# EBN_DUAL_V01.net
KiCad netlist of a schematic drawn in EAGLE
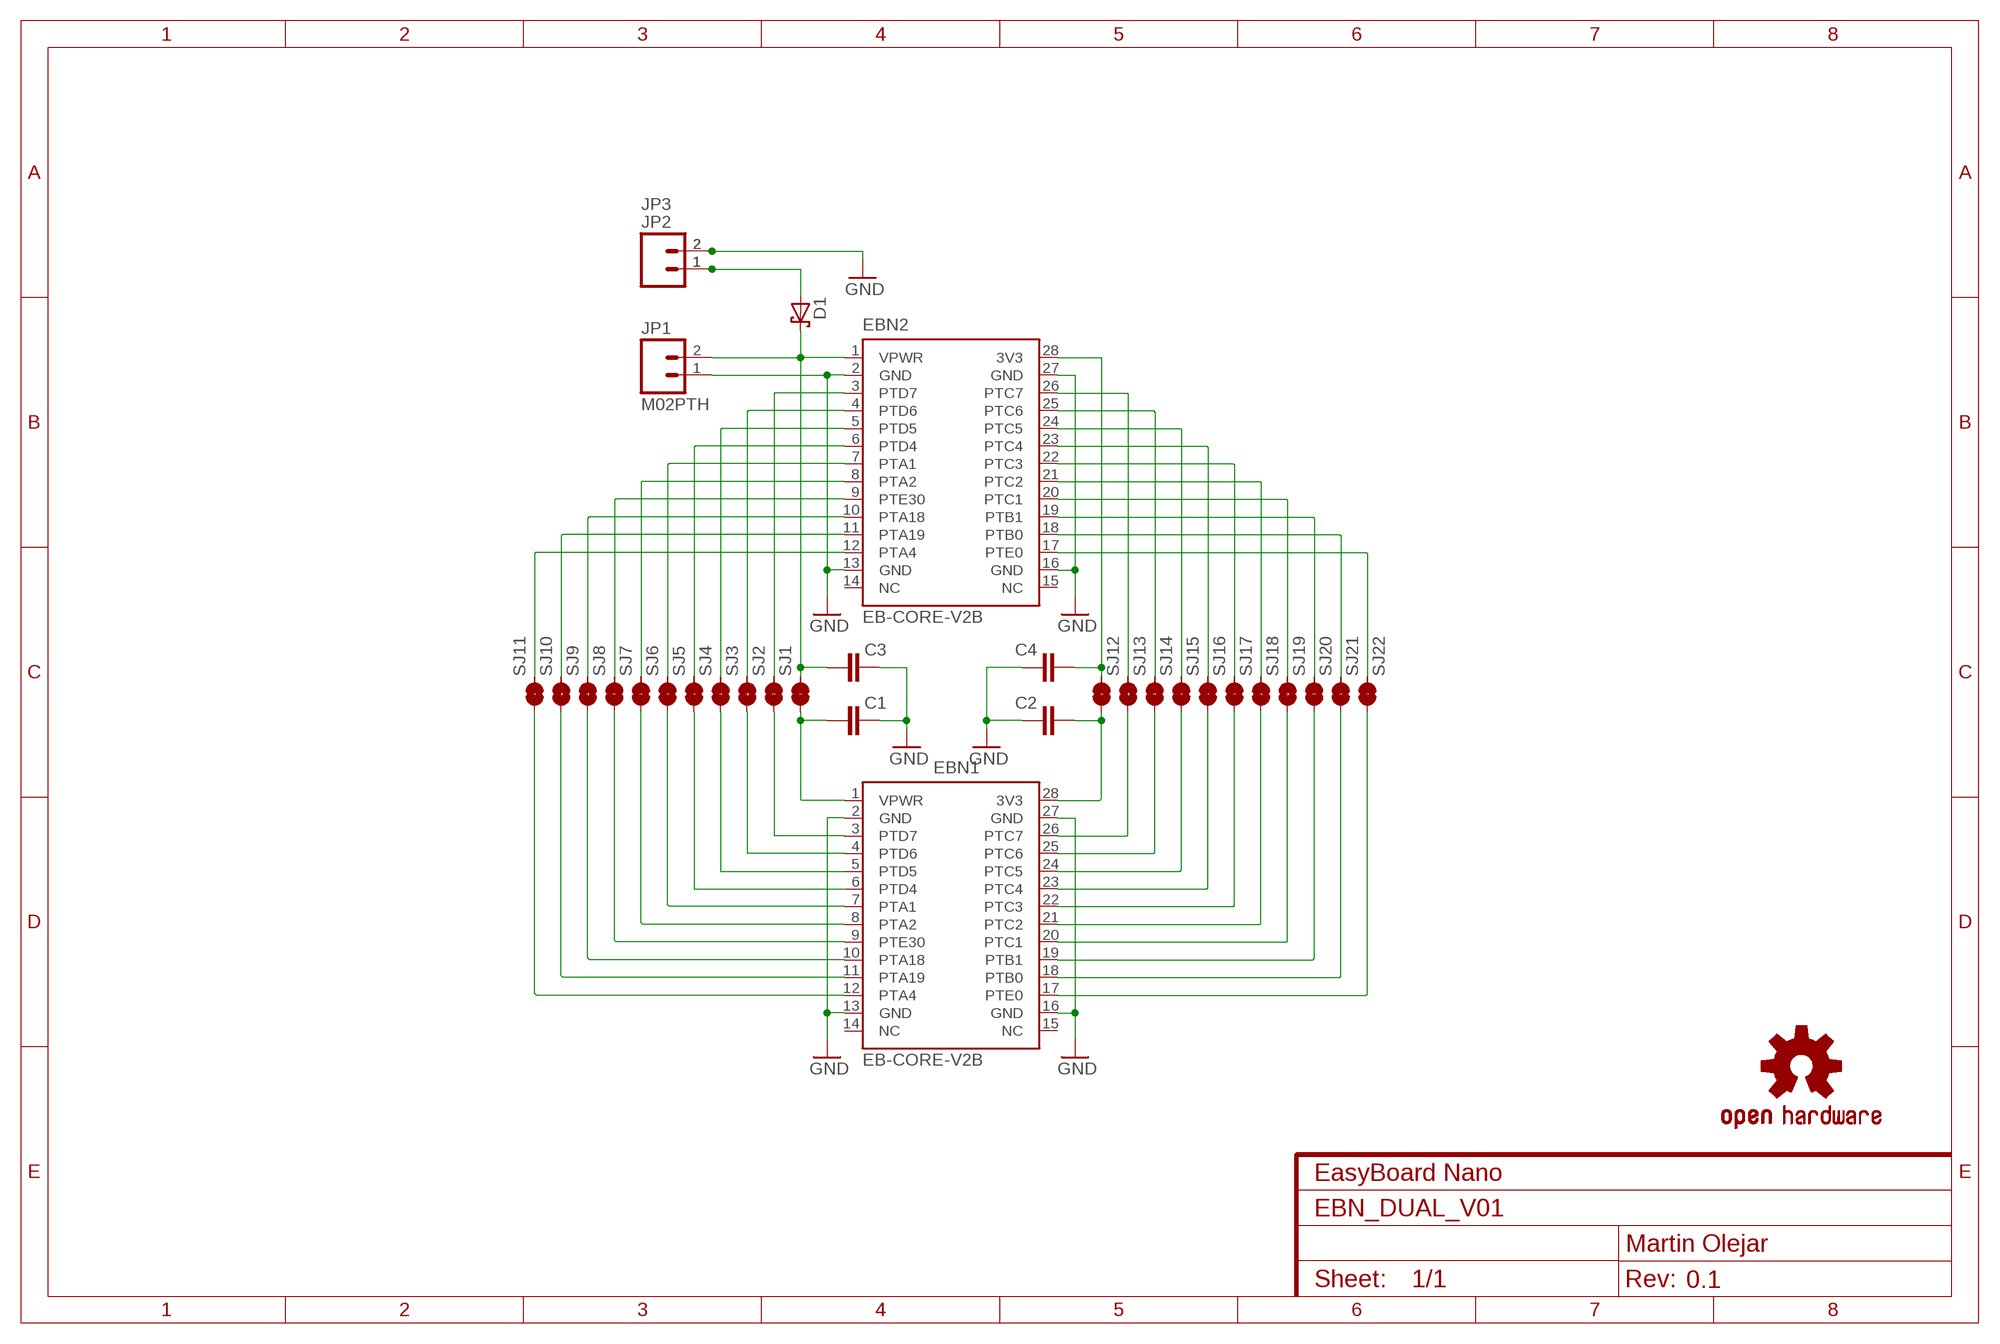
[diagram p0: schematic, sheet 1]

(export (version "E")
  (design (tool "Eeschema 10.0.6"))
  (components
    (comp (ref "C1")
      (value "C-EUC0603")
      (footprint "eagle-import:C0603")
      (libsource (lib "eagle-import") (part "C-EUC0603"))
    )
    (comp (ref "C2")
      (value "C-EUC0603")
      (footprint "eagle-import:C0603")
      (libsource (lib "eagle-import") (part "C-EUC0603"))
    )
    (comp (ref "C3")
      (value "C-EUC0603")
      (footprint "eagle-import:C0603")
      (libsource (lib "eagle-import") (part "C-EUC0603"))
    )
    (comp (ref "C4")
      (value "C-EUC0603")
      (footprint "eagle-import:C0603")
      (libsource (lib "eagle-import") (part "C-EUC0603"))
    )
    (comp (ref "D1")
      (value "PMEG2010BER-SHOTTKY-SOD123FL")
      (footprint "eagle-import:SOD-123FL")
      (libsource (lib "eagle-import") (part "-SHOTTKY-SOD123FLPMEG2010BER"))
    )
    (comp (ref "EBN1")
      (value "EB-CORE-V2B")
      (footprint "eagle-import:DIL28-6B")
      (libsource (lib "eagle-import") (part "EB-CORE-V2B"))
    )
    (comp (ref "EBN2")
      (value "EB-CORE-V2B")
      (footprint "eagle-import:DIL28-6B")
      (libsource (lib "eagle-import") (part "EB-CORE-V2B"))
    )
    (comp (ref "JP1")
      (value "M02PTH")
      (footprint "eagle-import:1X02")
      (libsource (lib "eagle-import") (part "M02PTH"))
    )
    (comp (ref "JP2")
      (value "M02SMD")
      (footprint "eagle-import:1X02-1.25MM_SMD")
      (libsource (lib "eagle-import") (part "M02SMD"))
    )
    (comp (ref "JP3")
      (value "M02PTH3")
      (footprint "eagle-import:1X02_LONGPADS")
      (libsource (lib "eagle-import") (part "M02PTH3"))
    )
    (comp (ref "LOGO1")
      (value "OSHW-LOGOS")
      (footprint "eagle-import:OSHW-LOGO-S")
      (libsource (lib "eagle-import") (part "OSHW-LOGOS"))
    )
    (comp (ref "SJ1")
      (value "SJS")
      (footprint "eagle-import:JUMPER-SMD-S1XS")
      (libsource (lib "eagle-import") (part "SJS"))
    )
    (comp (ref "SJ2")
      (value "SJS")
      (footprint "eagle-import:JUMPER-SMD-S1XS")
      (libsource (lib "eagle-import") (part "SJS"))
    )
    (comp (ref "SJ3")
      (value "SJS")
      (footprint "eagle-import:JUMPER-SMD-S1XS")
      (libsource (lib "eagle-import") (part "SJS"))
    )
    (comp (ref "SJ4")
      (value "SJS")
      (footprint "eagle-import:JUMPER-SMD-S1XS")
      (libsource (lib "eagle-import") (part "SJS"))
    )
    (comp (ref "SJ5")
      (value "SJS")
      (footprint "eagle-import:JUMPER-SMD-S1XS")
      (libsource (lib "eagle-import") (part "SJS"))
    )
    (comp (ref "SJ6")
      (value "SJS")
      (footprint "eagle-import:JUMPER-SMD-S1XS")
      (libsource (lib "eagle-import") (part "SJS"))
    )
    (comp (ref "SJ7")
      (value "SJS")
      (footprint "eagle-import:JUMPER-SMD-S1XS")
      (libsource (lib "eagle-import") (part "SJS"))
    )
    (comp (ref "SJ8")
      (value "SJS")
      (footprint "eagle-import:JUMPER-SMD-S1XS")
      (libsource (lib "eagle-import") (part "SJS"))
    )
    (comp (ref "SJ9")
      (value "SJS")
      (footprint "eagle-import:JUMPER-SMD-S1XS")
      (libsource (lib "eagle-import") (part "SJS"))
    )
    (comp (ref "SJ10")
      (value "SJS")
      (footprint "eagle-import:JUMPER-SMD-S1XS")
      (libsource (lib "eagle-import") (part "SJS"))
    )
    (comp (ref "SJ11")
      (value "SJS")
      (footprint "eagle-import:JUMPER-SMD-S1XS")
      (libsource (lib "eagle-import") (part "SJS"))
    )
    (comp (ref "SJ12")
      (value "SJS")
      (footprint "eagle-import:JUMPER-SMD-S1XS")
      (libsource (lib "eagle-import") (part "SJS"))
    )
    (comp (ref "SJ13")
      (value "SJS")
      (footprint "eagle-import:JUMPER-SMD-S1XS")
      (libsource (lib "eagle-import") (part "SJS"))
    )
    (comp (ref "SJ14")
      (value "SJS")
      (footprint "eagle-import:JUMPER-SMD-S1XS")
      (libsource (lib "eagle-import") (part "SJS"))
    )
    (comp (ref "SJ15")
      (value "SJS")
      (footprint "eagle-import:JUMPER-SMD-S1XS")
      (libsource (lib "eagle-import") (part "SJS"))
    )
    (comp (ref "SJ16")
      (value "SJS")
      (footprint "eagle-import:JUMPER-SMD-S1XS")
      (libsource (lib "eagle-import") (part "SJS"))
    )
    (comp (ref "SJ17")
      (value "SJS")
      (footprint "eagle-import:JUMPER-SMD-S1XS")
      (libsource (lib "eagle-import") (part "SJS"))
    )
    (comp (ref "SJ18")
      (value "SJS")
      (footprint "eagle-import:JUMPER-SMD-S1XS")
      (libsource (lib "eagle-import") (part "SJS"))
    )
    (comp (ref "SJ19")
      (value "SJS")
      (footprint "eagle-import:JUMPER-SMD-S1XS")
      (libsource (lib "eagle-import") (part "SJS"))
    )
    (comp (ref "SJ20")
      (value "SJS")
      (footprint "eagle-import:JUMPER-SMD-S1XS")
      (libsource (lib "eagle-import") (part "SJS"))
    )
    (comp (ref "SJ21")
      (value "SJS")
      (footprint "eagle-import:JUMPER-SMD-S1XS")
      (libsource (lib "eagle-import") (part "SJS"))
    )
    (comp (ref "SJ22")
      (value "SJS")
      (footprint "eagle-import:JUMPER-SMD-S1XS")
      (libsource (lib "eagle-import") (part "SJS"))
    )
  )
  (nets
    (net (code "1") (name "GND") (class "Default")
      (node (ref "C1") (pin "2") (pinfunction "2_2") (pintype "passive"))
      (node (ref "C2") (pin "1") (pinfunction "1_1") (pintype "passive"))
      (node (ref "C3") (pin "2") (pinfunction "2_2") (pintype "passive"))
      (node (ref "C4") (pin "1") (pinfunction "1_1") (pintype "passive"))
      (node (ref "EBN1") (pin "13") (pinfunction "GND_13") (pintype "power_in"))
      (node (ref "EBN1") (pin "16") (pinfunction "GND_16") (pintype "power_in"))
      (node (ref "EBN1") (pin "2") (pinfunction "GND_2") (pintype "power_in"))
      (node (ref "EBN1") (pin "27") (pinfunction "GND_27") (pintype "power_in"))
      (node (ref "EBN2") (pin "13") (pinfunction "GND_13") (pintype "power_in"))
      (node (ref "EBN2") (pin "16") (pinfunction "GND_16") (pintype "power_in"))
      (node (ref "EBN2") (pin "2") (pinfunction "GND_2") (pintype "power_in"))
      (node (ref "EBN2") (pin "27") (pinfunction "GND_27") (pintype "power_in"))
      (node (ref "JP1") (pin "1") (pinfunction "1_1") (pintype "passive"))
      (node (ref "JP2") (pin "2") (pinfunction "2_2") (pintype "passive"))
      (node (ref "JP3") (pin "2") (pinfunction "2_2") (pintype "passive"))
    )
    (net (code "2") (name "Net-(D1-PadA)") (class "Default")
      (node (ref "D1") (pin "A") (pinfunction "A_A") (pintype "passive"))
      (node (ref "JP2") (pin "1") (pinfunction "1_1") (pintype "passive"))
      (node (ref "JP3") (pin "1") (pinfunction "1_1") (pintype "passive"))
    )
    (net (code "3") (name "Net-(EBN1-3V3)") (class "Default")
      (node (ref "C2") (pin "2") (pinfunction "2_2") (pintype "passive"))
      (node (ref "EBN1") (pin "28") (pinfunction "3V3_28") (pintype "power_in"))
      (node (ref "SJ12") (pin "1") (pinfunction "1_1") (pintype "passive"))
    )
    (net (code "4") (name "Net-(EBN1-PTA1)") (class "Default")
      (node (ref "EBN1") (pin "7") (pinfunction "PTA1_7") (pintype "bidirectional"))
      (node (ref "SJ6") (pin "1") (pinfunction "1_1") (pintype "passive"))
    )
    (net (code "5") (name "Net-(EBN1-PTA2)") (class "Default")
      (node (ref "EBN1") (pin "8") (pinfunction "PTA2_8") (pintype "bidirectional"))
      (node (ref "SJ7") (pin "1") (pinfunction "1_1") (pintype "passive"))
    )
    (net (code "6") (name "Net-(EBN1-PTA4)") (class "Default")
      (node (ref "EBN1") (pin "12") (pinfunction "PTA4_12") (pintype "bidirectional"))
      (node (ref "SJ11") (pin "1") (pinfunction "1_1") (pintype "passive"))
    )
    (net (code "7") (name "Net-(EBN1-PTA18)") (class "Default")
      (node (ref "EBN1") (pin "10") (pinfunction "PTA18_10") (pintype "bidirectional"))
      (node (ref "SJ9") (pin "1") (pinfunction "1_1") (pintype "passive"))
    )
    (net (code "8") (name "Net-(EBN1-PTA19)") (class "Default")
      (node (ref "EBN1") (pin "11") (pinfunction "PTA19_11") (pintype "bidirectional"))
      (node (ref "SJ10") (pin "1") (pinfunction "1_1") (pintype "passive"))
    )
    (net (code "9") (name "Net-(EBN1-PTB0)") (class "Default")
      (node (ref "EBN1") (pin "18") (pinfunction "PTB0_18") (pintype "bidirectional"))
      (node (ref "SJ21") (pin "1") (pinfunction "1_1") (pintype "passive"))
    )
    (net (code "10") (name "Net-(EBN1-PTB1)") (class "Default")
      (node (ref "EBN1") (pin "19") (pinfunction "PTB1_19") (pintype "bidirectional"))
      (node (ref "SJ20") (pin "1") (pinfunction "1_1") (pintype "passive"))
    )
    (net (code "11") (name "Net-(EBN1-PTC1)") (class "Default")
      (node (ref "EBN1") (pin "20") (pinfunction "PTC1_20") (pintype "bidirectional"))
      (node (ref "SJ19") (pin "1") (pinfunction "1_1") (pintype "passive"))
    )
    (net (code "12") (name "Net-(EBN1-PTC2)") (class "Default")
      (node (ref "EBN1") (pin "21") (pinfunction "PTC2_21") (pintype "bidirectional"))
      (node (ref "SJ18") (pin "1") (pinfunction "1_1") (pintype "passive"))
    )
    (net (code "13") (name "Net-(EBN1-PTC3)") (class "Default")
      (node (ref "EBN1") (pin "22") (pinfunction "PTC3_22") (pintype "bidirectional"))
      (node (ref "SJ17") (pin "1") (pinfunction "1_1") (pintype "passive"))
    )
    (net (code "14") (name "Net-(EBN1-PTC4)") (class "Default")
      (node (ref "EBN1") (pin "23") (pinfunction "PTC4_23") (pintype "bidirectional"))
      (node (ref "SJ16") (pin "1") (pinfunction "1_1") (pintype "passive"))
    )
    (net (code "15") (name "Net-(EBN1-PTC5)") (class "Default")
      (node (ref "EBN1") (pin "24") (pinfunction "PTC5_24") (pintype "bidirectional"))
      (node (ref "SJ15") (pin "1") (pinfunction "1_1") (pintype "passive"))
    )
    (net (code "16") (name "Net-(EBN1-PTC6)") (class "Default")
      (node (ref "EBN1") (pin "25") (pinfunction "PTC6_25") (pintype "bidirectional"))
      (node (ref "SJ14") (pin "1") (pinfunction "1_1") (pintype "passive"))
    )
    (net (code "17") (name "Net-(EBN1-PTC7)") (class "Default")
      (node (ref "EBN1") (pin "26") (pinfunction "PTC7_26") (pintype "bidirectional"))
      (node (ref "SJ13") (pin "1") (pinfunction "1_1") (pintype "passive"))
    )
    (net (code "18") (name "Net-(EBN1-PTD4)") (class "Default")
      (node (ref "EBN1") (pin "6") (pinfunction "PTD4_6") (pintype "bidirectional"))
      (node (ref "SJ5") (pin "1") (pinfunction "1_1") (pintype "passive"))
    )
    (net (code "19") (name "Net-(EBN1-PTD5)") (class "Default")
      (node (ref "EBN1") (pin "5") (pinfunction "PTD5_5") (pintype "bidirectional"))
      (node (ref "SJ4") (pin "1") (pinfunction "1_1") (pintype "passive"))
    )
    (net (code "20") (name "Net-(EBN1-PTD6)") (class "Default")
      (node (ref "EBN1") (pin "4") (pinfunction "PTD6_4") (pintype "bidirectional"))
      (node (ref "SJ3") (pin "1") (pinfunction "1_1") (pintype "passive"))
    )
    (net (code "21") (name "Net-(EBN1-PTD7)") (class "Default")
      (node (ref "EBN1") (pin "3") (pinfunction "PTD7_3") (pintype "bidirectional"))
      (node (ref "SJ2") (pin "1") (pinfunction "1_1") (pintype "passive"))
    )
    (net (code "22") (name "Net-(EBN1-PTE0)") (class "Default")
      (node (ref "EBN1") (pin "17") (pinfunction "PTE0_17") (pintype "bidirectional"))
      (node (ref "SJ22") (pin "1") (pinfunction "1_1") (pintype "passive"))
    )
    (net (code "23") (name "Net-(EBN1-PTE30)") (class "Default")
      (node (ref "EBN1") (pin "9") (pinfunction "PTE30_9") (pintype "bidirectional"))
      (node (ref "SJ8") (pin "1") (pinfunction "1_1") (pintype "passive"))
    )
    (net (code "24") (name "Net-(EBN1-VPWR)") (class "Default")
      (node (ref "C1") (pin "1") (pinfunction "1_1") (pintype "passive"))
      (node (ref "EBN1") (pin "1") (pinfunction "VPWR_1") (pintype "power_in"))
      (node (ref "SJ1") (pin "1") (pinfunction "1_1") (pintype "passive"))
    )
    (net (code "25") (name "Net-(EBN2-3V3)") (class "Default")
      (node (ref "C4") (pin "2") (pinfunction "2_2") (pintype "passive"))
      (node (ref "EBN2") (pin "28") (pinfunction "3V3_28") (pintype "power_in"))
      (node (ref "SJ12") (pin "2") (pinfunction "2_2") (pintype "passive"))
    )
    (net (code "26") (name "Net-(EBN2-PTA1)") (class "Default")
      (node (ref "EBN2") (pin "7") (pinfunction "PTA1_7") (pintype "bidirectional"))
      (node (ref "SJ6") (pin "2") (pinfunction "2_2") (pintype "passive"))
    )
    (net (code "27") (name "Net-(EBN2-PTA2)") (class "Default")
      (node (ref "EBN2") (pin "8") (pinfunction "PTA2_8") (pintype "bidirectional"))
      (node (ref "SJ7") (pin "2") (pinfunction "2_2") (pintype "passive"))
    )
    (net (code "28") (name "Net-(EBN2-PTA4)") (class "Default")
      (node (ref "EBN2") (pin "12") (pinfunction "PTA4_12") (pintype "bidirectional"))
      (node (ref "SJ11") (pin "2") (pinfunction "2_2") (pintype "passive"))
    )
    (net (code "29") (name "Net-(EBN2-PTA18)") (class "Default")
      (node (ref "EBN2") (pin "10") (pinfunction "PTA18_10") (pintype "bidirectional"))
      (node (ref "SJ9") (pin "2") (pinfunction "2_2") (pintype "passive"))
    )
    (net (code "30") (name "Net-(EBN2-PTA19)") (class "Default")
      (node (ref "EBN2") (pin "11") (pinfunction "PTA19_11") (pintype "bidirectional"))
      (node (ref "SJ10") (pin "2") (pinfunction "2_2") (pintype "passive"))
    )
    (net (code "31") (name "Net-(EBN2-PTB0)") (class "Default")
      (node (ref "EBN2") (pin "18") (pinfunction "PTB0_18") (pintype "bidirectional"))
      (node (ref "SJ21") (pin "2") (pinfunction "2_2") (pintype "passive"))
    )
    (net (code "32") (name "Net-(EBN2-PTB1)") (class "Default")
      (node (ref "EBN2") (pin "19") (pinfunction "PTB1_19") (pintype "bidirectional"))
      (node (ref "SJ20") (pin "2") (pinfunction "2_2") (pintype "passive"))
    )
    (net (code "33") (name "Net-(EBN2-PTC1)") (class "Default")
      (node (ref "EBN2") (pin "20") (pinfunction "PTC1_20") (pintype "bidirectional"))
      (node (ref "SJ19") (pin "2") (pinfunction "2_2") (pintype "passive"))
    )
    (net (code "34") (name "Net-(EBN2-PTC2)") (class "Default")
      (node (ref "EBN2") (pin "21") (pinfunction "PTC2_21") (pintype "bidirectional"))
      (node (ref "SJ18") (pin "2") (pinfunction "2_2") (pintype "passive"))
    )
    (net (code "35") (name "Net-(EBN2-PTC3)") (class "Default")
      (node (ref "EBN2") (pin "22") (pinfunction "PTC3_22") (pintype "bidirectional"))
      (node (ref "SJ17") (pin "2") (pinfunction "2_2") (pintype "passive"))
    )
    (net (code "36") (name "Net-(EBN2-PTC4)") (class "Default")
      (node (ref "EBN2") (pin "23") (pinfunction "PTC4_23") (pintype "bidirectional"))
      (node (ref "SJ16") (pin "2") (pinfunction "2_2") (pintype "passive"))
    )
    (net (code "37") (name "Net-(EBN2-PTC5)") (class "Default")
      (node (ref "EBN2") (pin "24") (pinfunction "PTC5_24") (pintype "bidirectional"))
      (node (ref "SJ15") (pin "2") (pinfunction "2_2") (pintype "passive"))
    )
    (net (code "38") (name "Net-(EBN2-PTC6)") (class "Default")
      (node (ref "EBN2") (pin "25") (pinfunction "PTC6_25") (pintype "bidirectional"))
      (node (ref "SJ14") (pin "2") (pinfunction "2_2") (pintype "passive"))
    )
    (net (code "39") (name "Net-(EBN2-PTC7)") (class "Default")
      (node (ref "EBN2") (pin "26") (pinfunction "PTC7_26") (pintype "bidirectional"))
      (node (ref "SJ13") (pin "2") (pinfunction "2_2") (pintype "passive"))
    )
    (net (code "40") (name "Net-(EBN2-PTD4)") (class "Default")
      (node (ref "EBN2") (pin "6") (pinfunction "PTD4_6") (pintype "bidirectional"))
      (node (ref "SJ5") (pin "2") (pinfunction "2_2") (pintype "passive"))
    )
    (net (code "41") (name "Net-(EBN2-PTD5)") (class "Default")
      (node (ref "EBN2") (pin "5") (pinfunction "PTD5_5") (pintype "bidirectional"))
      (node (ref "SJ4") (pin "2") (pinfunction "2_2") (pintype "passive"))
    )
    (net (code "42") (name "Net-(EBN2-PTD6)") (class "Default")
      (node (ref "EBN2") (pin "4") (pinfunction "PTD6_4") (pintype "bidirectional"))
      (node (ref "SJ3") (pin "2") (pinfunction "2_2") (pintype "passive"))
    )
    (net (code "43") (name "Net-(EBN2-PTD7)") (class "Default")
      (node (ref "EBN2") (pin "3") (pinfunction "PTD7_3") (pintype "bidirectional"))
      (node (ref "SJ2") (pin "2") (pinfunction "2_2") (pintype "passive"))
    )
    (net (code "44") (name "Net-(EBN2-PTE0)") (class "Default")
      (node (ref "EBN2") (pin "17") (pinfunction "PTE0_17") (pintype "bidirectional"))
      (node (ref "SJ22") (pin "2") (pinfunction "2_2") (pintype "passive"))
    )
    (net (code "45") (name "Net-(EBN2-PTE30)") (class "Default")
      (node (ref "EBN2") (pin "9") (pinfunction "PTE30_9") (pintype "bidirectional"))
      (node (ref "SJ8") (pin "2") (pinfunction "2_2") (pintype "passive"))
    )
    (net (code "46") (name "Net-(EBN2-VPWR)") (class "Default")
      (node (ref "C3") (pin "1") (pinfunction "1_1") (pintype "passive"))
      (node (ref "D1") (pin "C") (pinfunction "C_C") (pintype "passive"))
      (node (ref "EBN2") (pin "1") (pinfunction "VPWR_1") (pintype "power_in"))
      (node (ref "JP1") (pin "2") (pinfunction "2_2") (pintype "passive"))
      (node (ref "SJ1") (pin "2") (pinfunction "2_2") (pintype "passive"))
    )
    (net (code "47") (name "unconnected-(EBN1-NC-Pad14)") (class "Default")
      (node (ref "EBN1") (pin "14") (pinfunction "NC_14") (pintype "no_connect"))
    )
    (net (code "48") (name "unconnected-(EBN1-NC-Pad15)") (class "Default")
      (node (ref "EBN1") (pin "15") (pinfunction "NC_15") (pintype "no_connect"))
    )
    (net (code "49") (name "unconnected-(EBN2-NC-Pad14)") (class "Default")
      (node (ref "EBN2") (pin "14") (pinfunction "NC_14") (pintype "no_connect"))
    )
    (net (code "50") (name "unconnected-(EBN2-NC-Pad15)") (class "Default")
      (node (ref "EBN2") (pin "15") (pinfunction "NC_15") (pintype "no_connect"))
    )
  )
)
